# Esquema_control_remoto.net
KiCad netlist of a schematic drawn in EAGLE
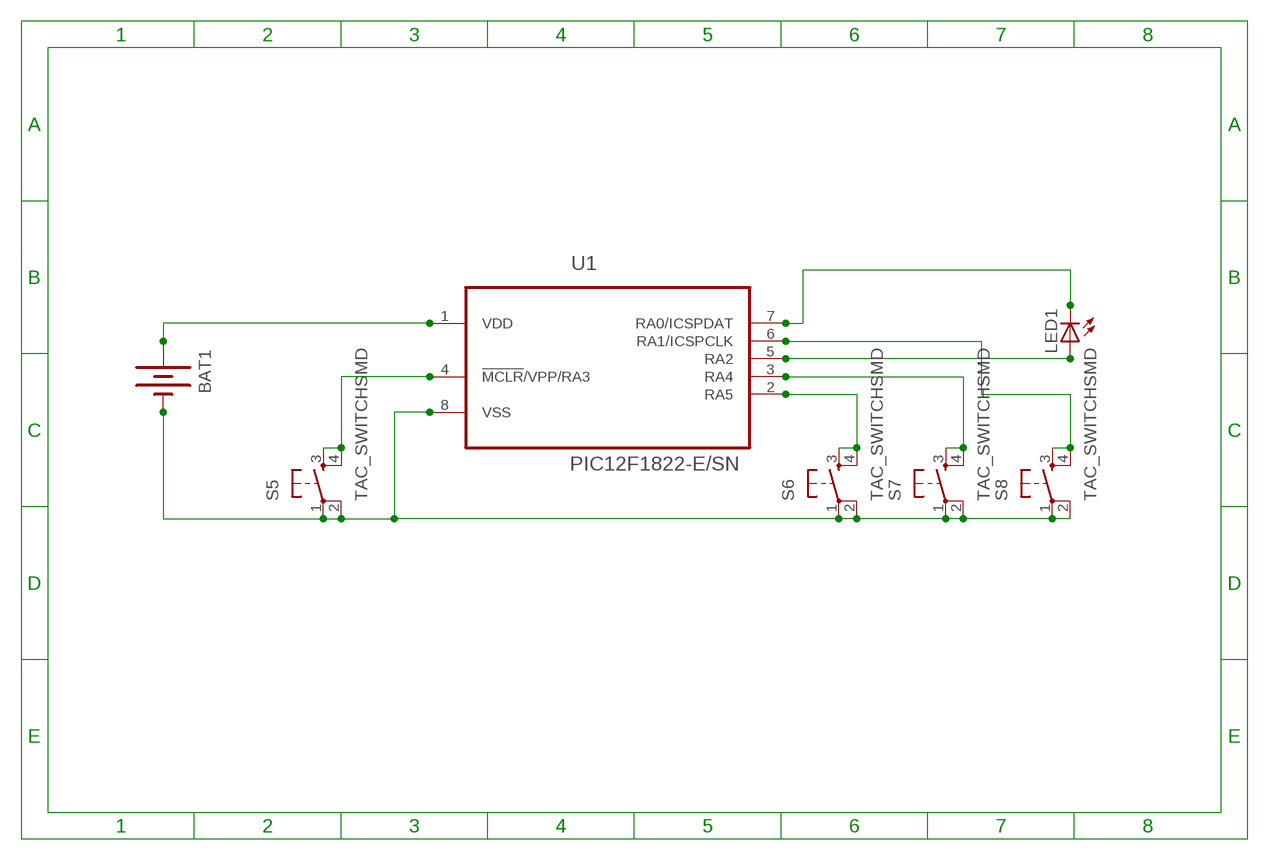
[diagram p0: schematic, sheet 1]

(export (version "E")
  (design (tool "Eeschema 10.0.6"))
  (components
    (comp (ref "BAT1")
      (value "BATTERY20SMD")
      (footprint "eagle-import:BATTCON_20MM")
      (libsource (lib "eagle-import") (part "BATTERY20SMD"))
    )
    (comp (ref "LED1")
      (value "LEDCHIPLED_1206")
      (footprint "eagle-import:CHIPLED_1206")
      (libsource (lib "eagle-import") (part "LEDCHIPLED_1206"))
    )
    (comp (ref "S5")
      (value "TAC_SWITCHSMD")
      (footprint "eagle-import:TACTILE-SWITCH-SMD")
      (libsource (lib "eagle-import") (part "TAC_SWITCHSMD"))
    )
    (comp (ref "S6")
      (value "TAC_SWITCHSMD")
      (footprint "eagle-import:TACTILE-SWITCH-SMD")
      (libsource (lib "eagle-import") (part "TAC_SWITCHSMD"))
    )
    (comp (ref "S7")
      (value "TAC_SWITCHSMD")
      (footprint "eagle-import:TACTILE-SWITCH-SMD")
      (libsource (lib "eagle-import") (part "TAC_SWITCHSMD"))
    )
    (comp (ref "S8")
      (value "TAC_SWITCHSMD")
      (footprint "eagle-import:TACTILE-SWITCH-SMD")
      (libsource (lib "eagle-import") (part "TAC_SWITCHSMD"))
    )
    (comp (ref "U1")
      (value "PIC12F1822-E/SN")
      (footprint "eagle-import:SOIC127P600X175-8N")
      (libsource (lib "eagle-import") (part "PIC12F1822-E/SN"))
    )
  )
  (nets
    (net (code "1") (name "Net-(BAT1-+)") (class "Default")
      (node (ref "BAT1") (pin "1") (pinfunction "+_1") (pintype "power_in"))
      (node (ref "U1") (pin "1") (pinfunction "VDD_1") (pintype "power_in"))
    )
    (net (code "2") (name "Net-(BAT1--)") (class "Default")
      (node (ref "BAT1") (pin "2") (pinfunction "-_2") (pintype "power_in"))
      (node (ref "S5") (pin "1") (pinfunction "1_1") (pintype "passive"))
      (node (ref "S5") (pin "2") (pinfunction "2_2") (pintype "passive"))
      (node (ref "S6") (pin "1") (pinfunction "1_1") (pintype "passive"))
      (node (ref "S6") (pin "2") (pinfunction "2_2") (pintype "passive"))
      (node (ref "S7") (pin "1") (pinfunction "1_1") (pintype "passive"))
      (node (ref "S7") (pin "2") (pinfunction "2_2") (pintype "passive"))
      (node (ref "S8") (pin "1") (pinfunction "1_1") (pintype "passive"))
      (node (ref "S8") (pin "2") (pinfunction "2_2") (pintype "passive"))
      (node (ref "U1") (pin "8") (pinfunction "VSS_8") (pintype "power_in"))
    )
    (net (code "3") (name "Net-(U1-RA0{slash}ICSPDAT)") (class "Default")
      (node (ref "LED1") (pin "C") (pinfunction "C_C") (pintype "passive"))
      (node (ref "U1") (pin "7") (pinfunction "RA0/ICSPDAT_7") (pintype "bidirectional"))
    )
    (net (code "4") (name "Net-(U1-RA1{slash}ICSPCLK)") (class "Default")
      (node (ref "S8") (pin "3") (pinfunction "3_3") (pintype "passive"))
      (node (ref "S8") (pin "4") (pinfunction "4_4") (pintype "passive"))
      (node (ref "U1") (pin "6") (pinfunction "RA1/ICSPCLK_6") (pintype "bidirectional"))
    )
    (net (code "5") (name "Net-(U1-RA2)") (class "Default")
      (node (ref "LED1") (pin "A") (pinfunction "A_A") (pintype "passive"))
      (node (ref "U1") (pin "5") (pinfunction "RA2_5") (pintype "bidirectional"))
    )
    (net (code "6") (name "Net-(U1-RA4)") (class "Default")
      (node (ref "S7") (pin "3") (pinfunction "3_3") (pintype "passive"))
      (node (ref "S7") (pin "4") (pinfunction "4_4") (pintype "passive"))
      (node (ref "U1") (pin "3") (pinfunction "RA4_3") (pintype "bidirectional"))
    )
    (net (code "7") (name "Net-(U1-RA5)") (class "Default")
      (node (ref "S6") (pin "3") (pinfunction "3_3") (pintype "passive"))
      (node (ref "S6") (pin "4") (pinfunction "4_4") (pintype "passive"))
      (node (ref "U1") (pin "2") (pinfunction "RA5_2") (pintype "bidirectional"))
    )
    (net (code "8") (name "Net-(U1-~{MCLR}{slash}VPP{slash}RA3)") (class "Default")
      (node (ref "S5") (pin "3") (pinfunction "3_3") (pintype "passive"))
      (node (ref "S5") (pin "4") (pinfunction "4_4") (pintype "passive"))
      (node (ref "U1") (pin "4") (pinfunction "~{MCLR}/VPP/RA3_4") (pintype "input"))
    )
  )
)
